# sz_1.net
KiCad netlist of a schematic drawn in Altium Designer
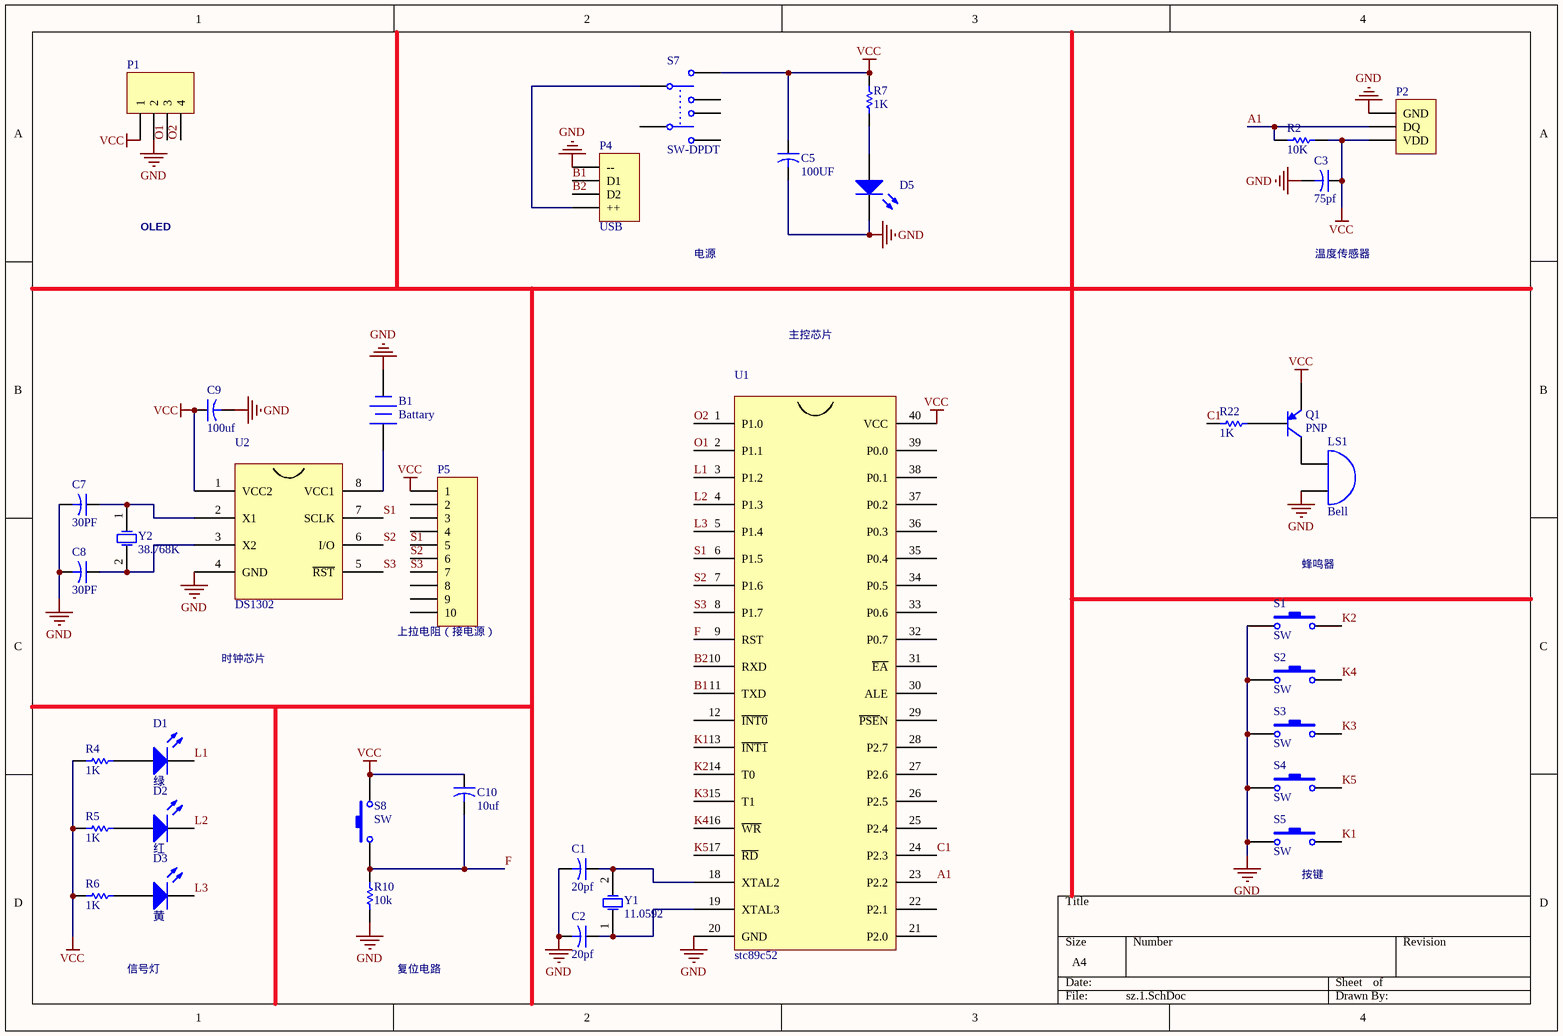
[diagram p0: sz.1.SchDoc]

(export (version "E")
  (design (tool "Eeschema 10.0.6"))
  (components
    (comp (ref "B1") (value "Battary") (footprint "Battary") (libsource (lib "YJ.1") (part "Battary")))
    (comp (ref "C1")
      (value "20pf")
      (footprint "CAPR5-4X5")
      (fields (field (name "PUBLISHER") "Altium Limited"))
      (libsource (lib "Miscellaneous Devices") (part "Cap2"))
    )
    (comp (ref "C2")
      (value "20pf")
      (footprint "CAPR5-4X5")
      (fields (field (name "PUBLISHER") "Altium Limited"))
      (libsource (lib "Miscellaneous Devices") (part "Cap2"))
    )
    (comp (ref "C3")
      (value "75pf")
      (footprint "CAPR5-4X5")
      (description "Capacitor")
      (fields (field (name "PUBLISHER") "Altium Limited"))
      (libsource (lib "Miscellaneous Devices") (part "Cap2"))
    )
    (comp (ref "C5")
      (value "100UF")
      (footprint "CAPR5-4X5")
      (description "Capacitor")
      (fields (field (name "PUBLISHER") "Altium Limited"))
      (libsource (lib "Miscellaneous Devices") (part "Cap2"))
    )
    (comp (ref "C7")
      (value "30PF")
      (footprint "CAPR5-4X5")
      (description "Capacitor")
      (fields (field (name "PUBLISHER") "Altium Limited"))
      (libsource (lib "Miscellaneous Devices") (part "Cap2"))
    )
    (comp (ref "C8")
      (value "30PF")
      (footprint "CAPR5-4X5")
      (description "Capacitor")
      (fields (field (name "PUBLISHER") "Altium Limited"))
      (libsource (lib "Miscellaneous Devices") (part "Cap2"))
    )
    (comp (ref "C9")
      (value "100uf")
      (footprint "CAPR5-4X5")
      (description "Capacitor")
      (fields (field (name "PUBLISHER") "Altium Limited"))
      (libsource (lib "Miscellaneous Devices") (part "Cap2"))
    )
    (comp (ref "C10")
      (value "10uf")
      (footprint "CAPR5-4X5")
      (description "Capacitor")
      (fields (field (name "PUBLISHER") "Altium Limited"))
      (libsource (lib "Miscellaneous Devices") (part "Cap2"))
    )
    (comp (ref "D1")
      (value "绿")
      (footprint "LED-1")
      (description "Typical RED GaAs LED")
      (fields (field (name "PUBLISHER") "Altium Limited"))
      (libsource (lib "Miscellaneous Devices") (part "LED1"))
    )
    (comp (ref "D2")
      (value "红")
      (footprint "LED-1")
      (description "Typical RED GaAs LED")
      (fields (field (name "PUBLISHER") "Altium Limited"))
      (libsource (lib "Miscellaneous Devices") (part "LED1"))
    )
    (comp (ref "D3")
      (value "黄")
      (footprint "LED-1")
      (description "Typical RED GaAs LED")
      (fields (field (name "PUBLISHER") "Altium Limited"))
      (libsource (lib "Miscellaneous Devices") (part "LED1"))
    )
    (comp (ref "D5")
      (value "LED1")
      (footprint "LED-1")
      (description "Typical RED GaAs LED")
      (fields (field (name "PUBLISHER") "Altium Limited"))
      (libsource (lib "Miscellaneous Devices") (part "LED1"))
    )
    (comp (ref "LS1") (value "Bell") (footprint "YJ.1:bell") (libsource (lib "YJ.1") (part "Bell")))
    (comp (ref "P1")
      (value "OLED")
      (footprint "HDR1X4")
      (description "Header, 4-Pin")
      (fields (field (name "PUBLISHER") "Altium Limited"))
      (libsource (lib "Miscellaneous Connectors") (part "Header 4"))
    )
    (comp (ref "P2")
      (value "Header 3")
      (footprint "HDR1X3")
      (description "Header, 3-Pin")
      (fields (field (name "PUBLISHER") "Altium Limited"))
      (libsource (lib "Miscellaneous Connectors") (part "Header 3"))
    )
    (comp (ref "P4")
      (value "USB")
      (footprint "HDR1X4")
      (description "Header, 4-Pin")
      (fields (field (name "PUBLISHER") "Altium Limited"))
      (libsource (lib "") (part "Header 4_1"))
    )
    (comp (ref "P5")
      (value "~")
      (footprint "HDR1X10")
      (description "Header, 10-Pin")
      (fields (field (name "PUBLISHER") "Altium Limited"))
      (libsource (lib "Miscellaneous Connectors") (part "Header 10"))
    )
    (comp (ref "Q1") (value "PNP") (footprint "PNP") (libsource (lib "YJ.1") (part "PNP")))
    (comp (ref "R2")
      (value "10K")
      (footprint "AXIAL-0.3")
      (description "Resistor")
      (fields (field (name "PUBLISHER") "Altium Limited"))
      (libsource (lib "Miscellaneous Devices") (part "Res1"))
    )
    (comp (ref "R4")
      (value "1K")
      (footprint "AXIAL-0.3")
      (description "Resistor")
      (fields (field (name "PUBLISHER") "Altium Limited"))
      (libsource (lib "Miscellaneous Devices") (part "Res1"))
    )
    (comp (ref "R5")
      (value "1K")
      (footprint "AXIAL-0.3")
      (description "Resistor")
      (fields (field (name "PUBLISHER") "Altium Limited"))
      (libsource (lib "Miscellaneous Devices") (part "Res1"))
    )
    (comp (ref "R6")
      (value "1K")
      (footprint "AXIAL-0.3")
      (description "Resistor")
      (fields (field (name "PUBLISHER") "Altium Limited"))
      (libsource (lib "Miscellaneous Devices") (part "Res1"))
    )
    (comp (ref "R7")
      (value "1K")
      (footprint "AXIAL-0.3")
      (description "Resistor")
      (fields (field (name "PUBLISHER") "Altium Limited"))
      (libsource (lib "Miscellaneous Devices") (part "Res1"))
    )
    (comp (ref "R10")
      (value "10k")
      (footprint "AXIAL-0.3")
      (description "Resistor")
      (fields (field (name "PUBLISHER") "Altium Limited"))
      (libsource (lib "Miscellaneous Devices") (part "Res1"))
    )
    (comp (ref "R22")
      (value "1K")
      (footprint "AXIAL-0.3")
      (description "Resistor")
      (fields (field (name "PUBLISHER") "Altium Limited"))
      (libsource (lib "Miscellaneous Devices") (part "Res1"))
    )
    (comp (ref "S1") (value "SW") (footprint "SW") (libsource (lib "YJ.1") (part "SW")))
    (comp (ref "S2") (value "SW") (footprint "SW") (libsource (lib "YJ.1") (part "SW")))
    (comp (ref "S3") (value "SW") (footprint "SW") (libsource (lib "YJ.1") (part "SW")))
    (comp (ref "S4") (value "SW") (footprint "SW") (libsource (lib "YJ.1") (part "SW")))
    (comp (ref "S5") (value "SW") (footprint "SW") (libsource (lib "YJ.1") (part "SW")))
    (comp (ref "S7")
      (value "SW-DPDT")
      (footprint "DPDT-6")
      (description "Double-Pole, Double-Throw Switch")
      (fields (field (name "PUBLISHER") "Altium Limited"))
      (libsource (lib "Miscellaneous Devices") (part "SW-DPDT"))
    )
    (comp (ref "S8") (value "SW") (footprint "SW") (libsource (lib "YJ.1") (part "SW")))
    (comp (ref "U1") (value "stc89c52") (footprint "stc89c52") (libsource (lib "YJ.1") (part "stc89c52")))
    (comp (ref "U2") (value "DS1302") (footprint "DS1302") (libsource (lib "YJ.1") (part "DS1302")))
    (comp (ref "Y1") (value "11.0592") (footprint "XTAL") (libsource (lib "YJ.1") (part "XTAL")))
    (comp (ref "Y2") (value "38.768K") (footprint "XTAL") (libsource (lib "YJ.1") (part "XTAL")))
  )
  (nets
    (net (code "1") (name "/A1") (class "Default")
      (node (ref "P2") (pin "2") (pinfunction "DQ_2") (pintype "passive"))
      (node (ref "R2") (pin "1") (pinfunction "1_1") (pintype "passive"))
      (node (ref "U1") (pin "23") (pinfunction "P2.2_23") (pintype "passive"))
    )
    (net (code "2") (name "/B1") (class "Default")
      (node (ref "P4") (pin "2") (pinfunction "D1_2") (pintype "passive"))
      (node (ref "U1") (pin "11") (pinfunction "TXD_11") (pintype "passive"))
    )
    (net (code "3") (name "/B2") (class "Default")
      (node (ref "P4") (pin "3") (pinfunction "D2_3") (pintype "passive"))
      (node (ref "U1") (pin "10") (pinfunction "RXD_10") (pintype "passive"))
    )
    (net (code "4") (name "/C1") (class "Default")
      (node (ref "R22") (pin "1") (pinfunction "1_1") (pintype "passive"))
      (node (ref "U1") (pin "24") (pinfunction "P2.3_24") (pintype "passive"))
    )
    (net (code "5") (name "/F") (class "Default")
      (node (ref "C10") (pin "2") (pinfunction "2_2") (pintype "passive"))
      (node (ref "R10") (pin "2") (pinfunction "2_2") (pintype "passive"))
      (node (ref "S8") (pin "1") (pinfunction "1_1") (pintype "passive"))
      (node (ref "U1") (pin "9") (pinfunction "RST_9") (pintype "passive"))
    )
    (net (code "6") (name "/K1") (class "Default")
      (node (ref "S5") (pin "2") (pinfunction "2_2") (pintype "passive"))
      (node (ref "U1") (pin "13") (pinfunction "~{INT1}_13") (pintype "passive"))
    )
    (net (code "7") (name "/K2") (class "Default")
      (node (ref "S1") (pin "2") (pinfunction "2_2") (pintype "passive"))
      (node (ref "U1") (pin "14") (pinfunction "T0_14") (pintype "passive"))
    )
    (net (code "8") (name "/K3") (class "Default")
      (node (ref "S3") (pin "2") (pinfunction "2_2") (pintype "passive"))
      (node (ref "U1") (pin "15") (pinfunction "T1_15") (pintype "passive"))
    )
    (net (code "9") (name "/K4") (class "Default")
      (node (ref "S2") (pin "2") (pinfunction "2_2") (pintype "passive"))
      (node (ref "U1") (pin "16") (pinfunction "~{WR}_16") (pintype "passive"))
    )
    (net (code "10") (name "/K5") (class "Default")
      (node (ref "S4") (pin "2") (pinfunction "2_2") (pintype "passive"))
      (node (ref "U1") (pin "17") (pinfunction "~{RD}_17") (pintype "passive"))
    )
    (net (code "11") (name "/L1") (class "Default")
      (node (ref "D1") (pin "2") (pinfunction "K_2") (pintype "passive"))
      (node (ref "U1") (pin "3") (pinfunction "P1.2_3") (pintype "passive"))
    )
    (net (code "12") (name "/L2") (class "Default")
      (node (ref "D2") (pin "2") (pinfunction "K_2") (pintype "passive"))
      (node (ref "U1") (pin "4") (pinfunction "P1.3_4") (pintype "passive"))
    )
    (net (code "13") (name "/L3") (class "Default")
      (node (ref "D3") (pin "2") (pinfunction "K_2") (pintype "passive"))
      (node (ref "U1") (pin "5") (pinfunction "P1.4_5") (pintype "passive"))
    )
    (net (code "14") (name "/O1") (class "Default")
      (node (ref "P1") (pin "3") (pinfunction "3_3") (pintype "passive"))
      (node (ref "U1") (pin "2") (pinfunction "P1.1_2") (pintype "passive"))
    )
    (net (code "15") (name "/O2") (class "Default")
      (node (ref "P1") (pin "4") (pinfunction "4_4") (pintype "passive"))
      (node (ref "U1") (pin "1") (pinfunction "P1.0_1") (pintype "passive"))
    )
    (net (code "16") (name "/S1") (class "Default")
      (node (ref "P5") (pin "5") (pinfunction "5_5") (pintype "passive"))
      (node (ref "U1") (pin "6") (pinfunction "P1.5_6") (pintype "passive"))
      (node (ref "U2") (pin "7") (pinfunction "SCLK_7") (pintype "passive"))
    )
    (net (code "17") (name "/S2") (class "Default")
      (node (ref "P5") (pin "6") (pinfunction "6_6") (pintype "passive"))
      (node (ref "U1") (pin "7") (pinfunction "P1.6_7") (pintype "passive"))
      (node (ref "U2") (pin "6") (pinfunction "I/O_6") (pintype "passive"))
    )
    (net (code "18") (name "/S3") (class "Default")
      (node (ref "P5") (pin "7") (pinfunction "7_7") (pintype "passive"))
      (node (ref "U1") (pin "8") (pinfunction "P1.7_8") (pintype "passive"))
      (node (ref "U2") (pin "5") (pinfunction "~{RST}_5") (pintype "passive"))
    )
    (net (code "19") (name "GND") (class "Default")
      (node (ref "B1") (pin "2") (pinfunction "-_2") (pintype "passive"))
      (node (ref "C1") (pin "2") (pinfunction "2_2") (pintype "passive"))
      (node (ref "C2") (pin "2") (pinfunction "2_2") (pintype "passive"))
      (node (ref "C3") (pin "2") (pinfunction "2_2") (pintype "passive"))
      (node (ref "C5") (pin "2") (pinfunction "2_2") (pintype "passive"))
      (node (ref "C7") (pin "2") (pinfunction "2_2") (pintype "passive"))
      (node (ref "C8") (pin "2") (pinfunction "2_2") (pintype "passive"))
      (node (ref "C9") (pin "2") (pinfunction "2_2") (pintype "passive"))
      (node (ref "D5") (pin "2") (pinfunction "K_2") (pintype "passive"))
      (node (ref "LS1") (pin "2") (pinfunction "B_2") (pintype "passive"))
      (node (ref "P1") (pin "2") (pinfunction "2_2") (pintype "passive"))
      (node (ref "P2") (pin "1") (pinfunction "GND_1") (pintype "passive"))
      (node (ref "P4") (pin "1") (pinfunction "--_1") (pintype "passive"))
      (node (ref "R10") (pin "1") (pinfunction "1_1") (pintype "passive"))
      (node (ref "S1") (pin "1") (pinfunction "1_1") (pintype "passive"))
      (node (ref "S2") (pin "1") (pinfunction "1_1") (pintype "passive"))
      (node (ref "S3") (pin "1") (pinfunction "1_1") (pintype "passive"))
      (node (ref "S4") (pin "1") (pinfunction "1_1") (pintype "passive"))
      (node (ref "S5") (pin "1") (pinfunction "1_1") (pintype "passive"))
      (node (ref "U1") (pin "20") (pinfunction "GND_20") (pintype "passive"))
      (node (ref "U2") (pin "4") (pinfunction "GND_4") (pintype "passive"))
    )
    (net (code "20") (name "Net-(B1-+)") (class "Default")
      (node (ref "B1") (pin "1") (pinfunction "+_1") (pintype "passive"))
      (node (ref "U2") (pin "8") (pinfunction "VCC1_8") (pintype "passive"))
    )
    (net (code "21") (name "Net-(D1-A)") (class "Default")
      (node (ref "D1") (pin "1") (pinfunction "A_1") (pintype "passive"))
      (node (ref "R4") (pin "2") (pinfunction "2_2") (pintype "passive"))
    )
    (net (code "22") (name "Net-(D2-A)") (class "Default")
      (node (ref "D2") (pin "1") (pinfunction "A_1") (pintype "passive"))
      (node (ref "R5") (pin "2") (pinfunction "2_2") (pintype "passive"))
    )
    (net (code "23") (name "Net-(D3-A)") (class "Default")
      (node (ref "D3") (pin "1") (pinfunction "A_1") (pintype "passive"))
      (node (ref "R6") (pin "2") (pinfunction "2_2") (pintype "passive"))
    )
    (net (code "24") (name "Net-(D5-A)") (class "Default")
      (node (ref "D5") (pin "1") (pinfunction "A_1") (pintype "passive"))
      (node (ref "R7") (pin "2") (pinfunction "2_2") (pintype "passive"))
    )
    (net (code "25") (name "Net-(LS1-A)") (class "Default")
      (node (ref "LS1") (pin "1") (pinfunction "A_1") (pintype "passive"))
      (node (ref "Q1") (pin "1") (pinfunction "C_1") (pintype "passive"))
    )
    (net (code "26") (name "Net-(P4-++)") (class "Default")
      (node (ref "P4") (pin "4") (pinfunction "++_4") (pintype "passive"))
      (node (ref "S7") (pin "1") (pinfunction "1_1") (pintype "passive"))
    )
    (net (code "27") (name "Net-(Q1-B)") (class "Default")
      (node (ref "Q1") (pin "2") (pinfunction "B_2") (pintype "passive"))
      (node (ref "R22") (pin "2") (pinfunction "2_2") (pintype "passive"))
    )
    (net (code "28") (name "Net-(U1-XTAL2)") (class "Default")
      (node (ref "C1") (pin "1") (pinfunction "1_1") (pintype "passive"))
      (node (ref "U1") (pin "18") (pinfunction "XTAL2_18") (pintype "passive"))
      (node (ref "Y1") (pin "2") (pinfunction "OSC2_2") (pintype "passive"))
    )
    (net (code "29") (name "Net-(U1-XTAL3)") (class "Default")
      (node (ref "C2") (pin "1") (pinfunction "1_1") (pintype "passive"))
      (node (ref "U1") (pin "19") (pinfunction "XTAL3_19") (pintype "passive"))
      (node (ref "Y1") (pin "1") (pinfunction "OSC1_1") (pintype "passive"))
    )
    (net (code "30") (name "Net-(U2-X1)") (class "Default")
      (node (ref "C7") (pin "1") (pinfunction "1_1") (pintype "passive"))
      (node (ref "U2") (pin "2") (pinfunction "X1_2") (pintype "passive"))
      (node (ref "Y2") (pin "1") (pinfunction "OSC1_1") (pintype "passive"))
    )
    (net (code "31") (name "Net-(U2-X2)") (class "Default")
      (node (ref "C8") (pin "1") (pinfunction "1_1") (pintype "passive"))
      (node (ref "U2") (pin "3") (pinfunction "X2_3") (pintype "passive"))
      (node (ref "Y2") (pin "2") (pinfunction "OSC2_2") (pintype "passive"))
    )
    (net (code "32") (name "VCC") (class "Default")
      (node (ref "C10") (pin "1") (pinfunction "1_1") (pintype "passive"))
      (node (ref "C3") (pin "1") (pinfunction "1_1") (pintype "passive"))
      (node (ref "C5") (pin "1") (pinfunction "1_1") (pintype "passive"))
      (node (ref "C9") (pin "1") (pinfunction "1_1") (pintype "passive"))
      (node (ref "P1") (pin "1") (pinfunction "1_1") (pintype "passive"))
      (node (ref "P2") (pin "3") (pinfunction "VDD_3") (pintype "passive"))
      (node (ref "P5") (pin "1") (pinfunction "1_1") (pintype "passive"))
      (node (ref "Q1") (pin "3") (pinfunction "E_3") (pintype "passive"))
      (node (ref "R2") (pin "2") (pinfunction "2_2") (pintype "passive"))
      (node (ref "R4") (pin "1") (pinfunction "1_1") (pintype "passive"))
      (node (ref "R5") (pin "1") (pinfunction "1_1") (pintype "passive"))
      (node (ref "R6") (pin "1") (pinfunction "1_1") (pintype "passive"))
      (node (ref "R7") (pin "1") (pinfunction "1_1") (pintype "passive"))
      (node (ref "S7") (pin "2") (pinfunction "2_2") (pintype "passive"))
      (node (ref "S8") (pin "2") (pinfunction "2_2") (pintype "passive"))
      (node (ref "U1") (pin "40") (pinfunction "VCC_40") (pintype "passive"))
      (node (ref "U2") (pin "1") (pinfunction "VCC2_1") (pintype "passive"))
    )
    (net (code "33") (name "unconnected-(P5-Pad2)") (class "Default")
      (node (ref "P5") (pin "2") (pinfunction "2_2") (pintype "passive"))
    )
    (net (code "34") (name "unconnected-(P5-Pad3)") (class "Default")
      (node (ref "P5") (pin "3") (pinfunction "3_3") (pintype "passive"))
    )
    (net (code "35") (name "unconnected-(P5-Pad4)") (class "Default")
      (node (ref "P5") (pin "4") (pinfunction "4_4") (pintype "passive"))
    )
    (net (code "36") (name "unconnected-(P5-Pad8)") (class "Default")
      (node (ref "P5") (pin "8") (pinfunction "8_8") (pintype "passive"))
    )
    (net (code "37") (name "unconnected-(P5-Pad9)") (class "Default")
      (node (ref "P5") (pin "9") (pinfunction "9_9") (pintype "passive"))
    )
    (net (code "38") (name "unconnected-(P5-Pad10)") (class "Default")
      (node (ref "P5") (pin "10") (pinfunction "10_10") (pintype "passive"))
    )
    (net (code "39") (name "unconnected-(S7-Pad3)") (class "Default")
      (node (ref "S7") (pin "3") (pinfunction "3_3") (pintype "passive"))
    )
    (net (code "40") (name "unconnected-(S7-Pad4)") (class "Default")
      (node (ref "S7") (pin "4") (pinfunction "4_4") (pintype "passive"))
    )
    (net (code "41") (name "unconnected-(S7-Pad5)") (class "Default")
      (node (ref "S7") (pin "5") (pinfunction "5_5") (pintype "passive"))
    )
    (net (code "42") (name "unconnected-(S7-Pad6)") (class "Default")
      (node (ref "S7") (pin "6") (pinfunction "6_6") (pintype "passive"))
    )
    (net (code "43") (name "unconnected-(U1-ALE-Pad30)") (class "Default")
      (node (ref "U1") (pin "30") (pinfunction "ALE_30") (pintype "passive"))
    )
    (net (code "44") (name "unconnected-(U1-P0.0-Pad39)") (class "Default")
      (node (ref "U1") (pin "39") (pinfunction "P0.0_39") (pintype "passive"))
    )
    (net (code "45") (name "unconnected-(U1-P0.1-Pad38)") (class "Default")
      (node (ref "U1") (pin "38") (pinfunction "P0.1_38") (pintype "passive"))
    )
    (net (code "46") (name "unconnected-(U1-P0.2-Pad37)") (class "Default")
      (node (ref "U1") (pin "37") (pinfunction "P0.2_37") (pintype "passive"))
    )
    (net (code "47") (name "unconnected-(U1-P0.3-Pad36)") (class "Default")
      (node (ref "U1") (pin "36") (pinfunction "P0.3_36") (pintype "passive"))
    )
    (net (code "48") (name "unconnected-(U1-P0.4-Pad35)") (class "Default")
      (node (ref "U1") (pin "35") (pinfunction "P0.4_35") (pintype "passive"))
    )
    (net (code "49") (name "unconnected-(U1-P0.5-Pad34)") (class "Default")
      (node (ref "U1") (pin "34") (pinfunction "P0.5_34") (pintype "passive"))
    )
    (net (code "50") (name "unconnected-(U1-P0.6-Pad33)") (class "Default")
      (node (ref "U1") (pin "33") (pinfunction "P0.6_33") (pintype "passive"))
    )
    (net (code "51") (name "unconnected-(U1-P0.7-Pad32)") (class "Default")
      (node (ref "U1") (pin "32") (pinfunction "P0.7_32") (pintype "passive"))
    )
    (net (code "52") (name "unconnected-(U1-P2.0-Pad21)") (class "Default")
      (node (ref "U1") (pin "21") (pinfunction "P2.0_21") (pintype "passive"))
    )
    (net (code "53") (name "unconnected-(U1-P2.1-Pad22)") (class "Default")
      (node (ref "U1") (pin "22") (pinfunction "P2.1_22") (pintype "passive"))
    )
    (net (code "54") (name "unconnected-(U1-P2.4-Pad25)") (class "Default")
      (node (ref "U1") (pin "25") (pinfunction "P2.4_25") (pintype "passive"))
    )
    (net (code "55") (name "unconnected-(U1-P2.5-Pad26)") (class "Default")
      (node (ref "U1") (pin "26") (pinfunction "P2.5_26") (pintype "passive"))
    )
    (net (code "56") (name "unconnected-(U1-P2.6-Pad27)") (class "Default")
      (node (ref "U1") (pin "27") (pinfunction "P2.6_27") (pintype "passive"))
    )
    (net (code "57") (name "unconnected-(U1-P2.7-Pad28)") (class "Default")
      (node (ref "U1") (pin "28") (pinfunction "P2.7_28") (pintype "passive"))
    )
    (net (code "58") (name "unconnected-(U1-~{EA}-Pad31)") (class "Default")
      (node (ref "U1") (pin "31") (pinfunction "~{EA}_31") (pintype "passive"))
    )
    (net (code "59") (name "unconnected-(U1-~{INT0}-Pad12)") (class "Default")
      (node (ref "U1") (pin "12") (pinfunction "~{INT0}_12") (pintype "passive"))
    )
    (net (code "60") (name "unconnected-(U1-~{PSE}N-Pad29)") (class "Default")
      (node (ref "U1") (pin "29") (pinfunction "~{PSE}N_29") (pintype "passive"))
    )
  )
)
